# HBridge.net
KiCad netlist of a schematic drawn in Altium Designer
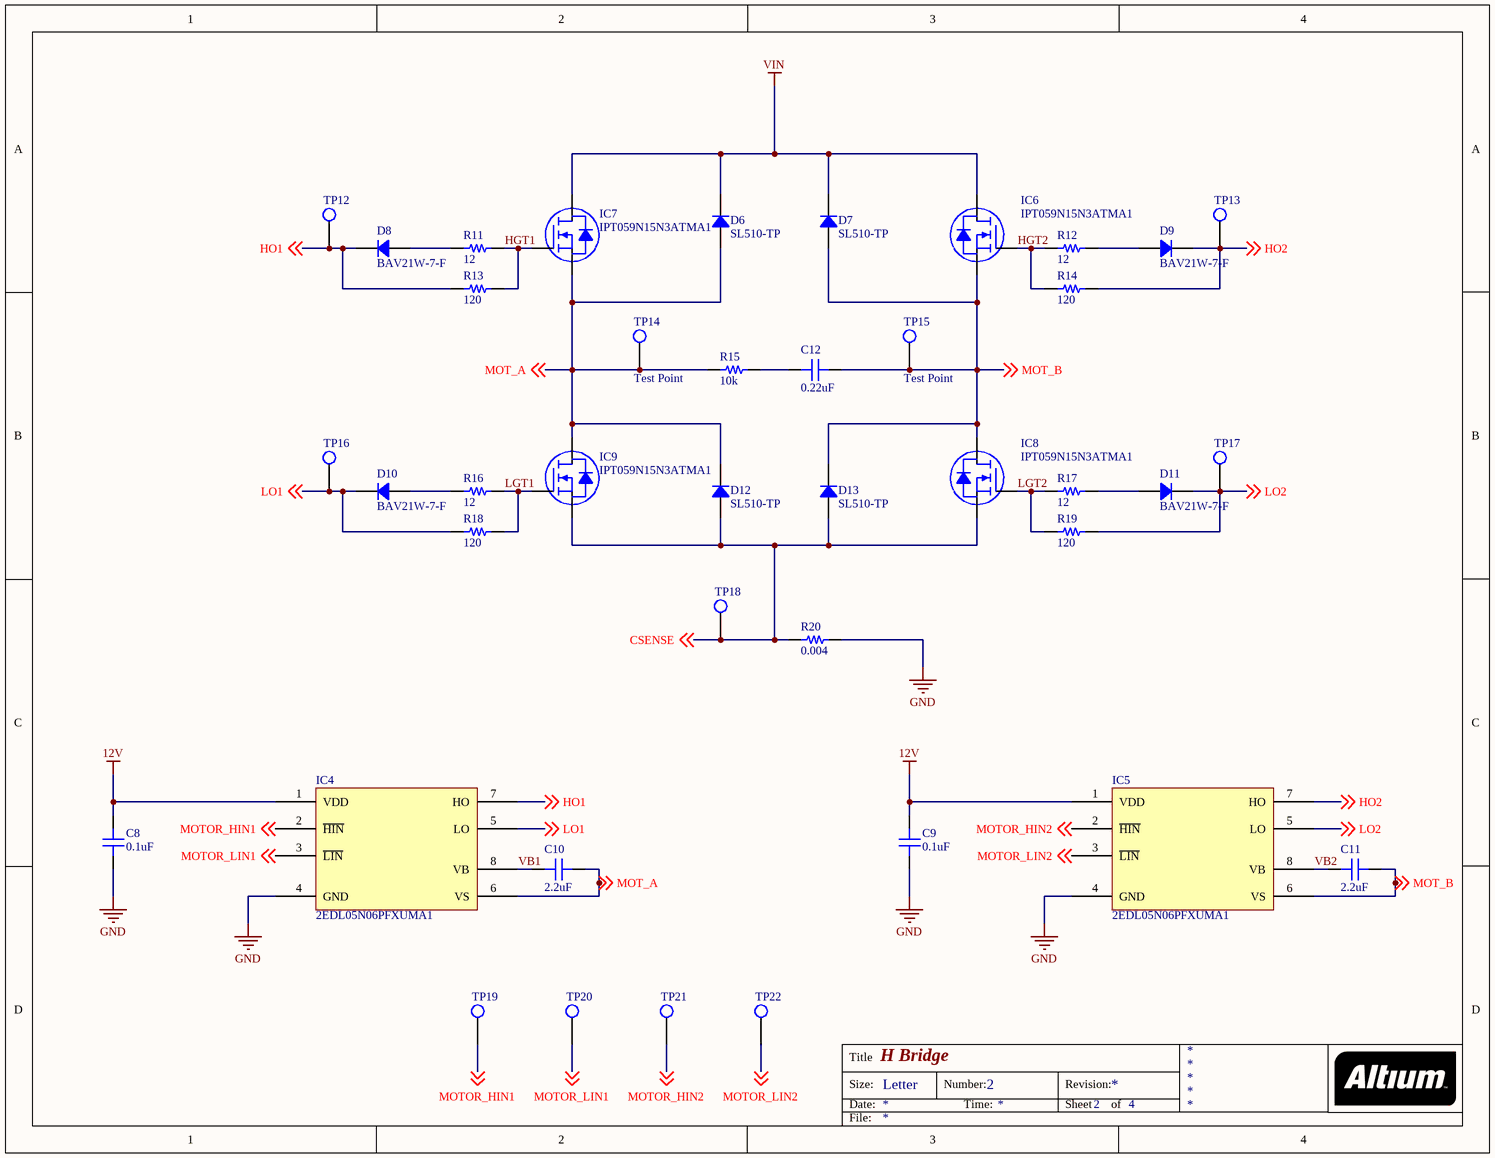
[diagram p0: HBridge.SchDoc]

(export (version "E")
  (design (tool "Eeschema 10.0.6"))
  (components
    (comp (ref "C8")
      (value "0.1uF")
      (footprint "CAP 0603/1608")
      (description "CAP CER 0.1UF 16V X7R 0603")
      (fields (field (name "PART NUMBER") "CC0603KPX7R7BB104") (field (name "MANUFACTURER") "Yageo"))
      (libsource (lib "Celestial Library Database") (part "Capacitor"))
    )
    (comp (ref "C9")
      (value "0.1uF")
      (footprint "CAP 0603/1608")
      (description "CAP CER 0.1UF 16V X7R 0603")
      (fields (field (name "PART NUMBER") "CC0603KPX7R7BB104") (field (name "MANUFACTURER") "Yageo"))
      (libsource (lib "Celestial Library Database") (part "Capacitor"))
    )
    (comp (ref "C10")
      (value "2.2uF")
      (footprint "CAP 0805/2012")
      (description "CAP CER 2.2UF 25V X6S 0805")
      (fields
        (field (name "PART NUMBER") "GRM219C81E225KE15D")
        (field (name "MANUFACTURER") "Murata Electronics North America")
      )
      (libsource (lib "Celestial Library Database") (part "Capacitor"))
    )
    (comp (ref "C11")
      (value "2.2uF")
      (footprint "CAP 0805/2012")
      (description "CAP CER 2.2UF 25V X6S 0805")
      (fields
        (field (name "PART NUMBER") "GRM219C81E225KE15D")
        (field (name "MANUFACTURER") "Murata Electronics North America")
      )
      (libsource (lib "Celestial Library Database") (part "Capacitor"))
    )
    (comp (ref "C12")
      (value "0.22uF")
      (footprint "CAP 1206/3216")
      (description "CAP CER 0.22UF 250V X7T 1206")
      (fields
        (field (name "PART NUMBER") "C3216X7T2E224K160AA")
        (field (name "MANUFACTURER") "TDK Corporation")
      )
      (libsource (lib "Celestial Library Database") (part "Capacitor"))
    )
    (comp (ref "D6")
      (value "SL510-TP")
      (footprint "ST DO214AB SMC")
      (description "DIODE SCHOTTKY 100V 5A DO214AB")
      (fields (field (name "MANUFACTURER") "Micro Commercial Co"))
      (libsource (lib "Celestial Library Database") (part "Diode"))
    )
    (comp (ref "D7")
      (value "SL510-TP")
      (footprint "ST DO214AB SMC")
      (description "DIODE SCHOTTKY 100V 5A DO214AB")
      (fields (field (name "MANUFACTURER") "Micro Commercial Co"))
      (libsource (lib "Celestial Library Database") (part "Diode"))
    )
    (comp (ref "D8")
      (value "BAV21W-7-F")
      (footprint "SOD-123")
      (description "DIODE GEN PURP 200V 200MA SOD123")
      (fields (field (name "MANUFACTURER") "Diodes Incorporated"))
      (libsource (lib "Celestial Library Database") (part "Diode"))
    )
    (comp (ref "D9")
      (value "BAV21W-7-F")
      (footprint "SOD-123")
      (description "DIODE GEN PURP 200V 200MA SOD123")
      (fields (field (name "MANUFACTURER") "Diodes Incorporated"))
      (libsource (lib "Celestial Library Database") (part "Diode"))
    )
    (comp (ref "D10")
      (value "BAV21W-7-F")
      (footprint "SOD-123")
      (description "DIODE GEN PURP 200V 200MA SOD123")
      (fields (field (name "MANUFACTURER") "Diodes Incorporated"))
      (libsource (lib "Celestial Library Database") (part "Diode"))
    )
    (comp (ref "D11")
      (value "BAV21W-7-F")
      (footprint "SOD-123")
      (description "DIODE GEN PURP 200V 200MA SOD123")
      (fields (field (name "MANUFACTURER") "Diodes Incorporated"))
      (libsource (lib "Celestial Library Database") (part "Diode"))
    )
    (comp (ref "D12")
      (value "SL510-TP")
      (footprint "ST DO214AB SMC")
      (description "DIODE SCHOTTKY 100V 5A DO214AB")
      (fields (field (name "MANUFACTURER") "Micro Commercial Co"))
      (libsource (lib "Celestial Library Database") (part "Diode"))
    )
    (comp (ref "D13")
      (value "SL510-TP")
      (footprint "ST DO214AB SMC")
      (description "DIODE SCHOTTKY 100V 5A DO214AB")
      (fields (field (name "MANUFACTURER") "Micro Commercial Co"))
      (libsource (lib "Celestial Library Database") (part "Diode"))
    )
    (comp (ref "IC4")
      (value "2EDL05N06PFXUMA1")
      (footprint "Infineon PG-DSO-8")
      (description "IC DRIVER GATE HALF BRIDGE 8DSO")
      (fields (field (name "MANUFACTURER") "Infineon Technologies"))
      (libsource (lib "Celestial Library Database") (part "Infineon 2EDL05N06PF"))
    )
    (comp (ref "IC5")
      (value "2EDL05N06PFXUMA1")
      (footprint "Infineon PG-DSO-8")
      (description "IC DRIVER GATE HALF BRIDGE 8DSO")
      (fields (field (name "MANUFACTURER") "Infineon Technologies"))
      (libsource (lib "Celestial Library Database") (part "Infineon 2EDL05N06PF"))
    )
    (comp (ref "IC6")
      (value "IPT059N15N3ATMA1")
      (footprint "INFINEON PG-HSOF-8-1")
      (description "MOSFET N-CH 150V 155A 8HSOF")
      (fields (field (name "MANUFACTURER") "Infineon Technologies"))
      (libsource (lib "Celestial Library Database") (part "INFINEON MOSFET IPT059N15N3"))
    )
    (comp (ref "IC7")
      (value "IPT059N15N3ATMA1")
      (footprint "INFINEON PG-HSOF-8-1")
      (description "MOSFET N-CH 150V 155A 8HSOF")
      (fields (field (name "MANUFACTURER") "Infineon Technologies"))
      (libsource (lib "") (part "INFINEON MOSFET IPT059N15N3_1"))
    )
    (comp (ref "IC8")
      (value "IPT059N15N3ATMA1")
      (footprint "INFINEON PG-HSOF-8-1")
      (description "MOSFET N-CH 150V 155A 8HSOF")
      (fields (field (name "MANUFACTURER") "Infineon Technologies"))
      (libsource (lib "Celestial Library Database") (part "INFINEON MOSFET IPT059N15N3"))
    )
    (comp (ref "IC9")
      (value "IPT059N15N3ATMA1")
      (footprint "INFINEON PG-HSOF-8-1")
      (description "MOSFET N-CH 150V 155A 8HSOF")
      (fields (field (name "MANUFACTURER") "Infineon Technologies"))
      (libsource (lib "") (part "INFINEON MOSFET IPT059N15N3_1"))
    )
    (comp (ref "R11")
      (value "12")
      (footprint "RES 1206/3216")
      (description "RES SMD 12 OHM 5% 1/4W 1206")
      (fields
        (field (name "PART NUMBER") "ERJ-8GEYJ120V")
        (field (name "MANUFACTURER") "Panasonic Electronic Components")
      )
      (libsource (lib "Celestial Library Database") (part "Resistor"))
    )
    (comp (ref "R12")
      (value "12")
      (footprint "RES 1206/3216")
      (description "RES SMD 12 OHM 5% 1/4W 1206")
      (fields
        (field (name "PART NUMBER") "ERJ-8GEYJ120V")
        (field (name "MANUFACTURER") "Panasonic Electronic Components")
      )
      (libsource (lib "Celestial Library Database") (part "Resistor"))
    )
    (comp (ref "R13")
      (value "120")
      (footprint "RES 1206/3216")
      (description "RES SMD 120 OHM 5% 1/4W 1206")
      (fields
        (field (name "PART NUMBER") "ERJ-8GEYJ121V")
        (field (name "MANUFACTURER") "Panasonic Electronic Components")
      )
      (libsource (lib "Celestial Library Database") (part "Resistor"))
    )
    (comp (ref "R14")
      (value "120")
      (footprint "RES 1206/3216")
      (description "RES SMD 120 OHM 5% 1/4W 1206")
      (fields
        (field (name "PART NUMBER") "ERJ-8GEYJ121V")
        (field (name "MANUFACTURER") "Panasonic Electronic Components")
      )
      (libsource (lib "Celestial Library Database") (part "Resistor"))
    )
    (comp (ref "R15")
      (value "10k")
      (footprint "RES 0805/2012")
      (description "RES SMD 10K OHM 5% 1/8W 0805")
      (fields
        (field (name "PART NUMBER") "ERJ-6GEYJ103V")
        (field (name "MANUFACTURER") "Panasonic Electronic Components")
      )
      (libsource (lib "Celestial Library Database") (part "Resistor"))
    )
    (comp (ref "R16")
      (value "12")
      (footprint "RES 1206/3216")
      (description "RES SMD 12 OHM 5% 1/4W 1206")
      (fields
        (field (name "PART NUMBER") "ERJ-8GEYJ120V")
        (field (name "MANUFACTURER") "Panasonic Electronic Components")
      )
      (libsource (lib "Celestial Library Database") (part "Resistor"))
    )
    (comp (ref "R17")
      (value "12")
      (footprint "RES 1206/3216")
      (description "RES SMD 12 OHM 5% 1/4W 1206")
      (fields
        (field (name "PART NUMBER") "ERJ-8GEYJ120V")
        (field (name "MANUFACTURER") "Panasonic Electronic Components")
      )
      (libsource (lib "Celestial Library Database") (part "Resistor"))
    )
    (comp (ref "R18")
      (value "120")
      (footprint "RES 1206/3216")
      (description "RES SMD 120 OHM 5% 1/4W 1206")
      (fields
        (field (name "PART NUMBER") "ERJ-8GEYJ121V")
        (field (name "MANUFACTURER") "Panasonic Electronic Components")
      )
      (libsource (lib "Celestial Library Database") (part "Resistor"))
    )
    (comp (ref "R19")
      (value "120")
      (footprint "RES 1206/3216")
      (description "RES SMD 120 OHM 5% 1/4W 1206")
      (fields
        (field (name "PART NUMBER") "ERJ-8GEYJ121V")
        (field (name "MANUFACTURER") "Panasonic Electronic Components")
      )
      (libsource (lib "Celestial Library Database") (part "Resistor"))
    )
    (comp (ref "R20")
      (value "0.004")
      (footprint "STACKPOLE CSR2512")
      (description "RES SMD 0.004 OHM 1% 1W 2512")
      (fields
        (field (name "PART NUMBER") "ERJ-MP4MF4M0U")
        (field (name "MANUFACTURER") "Panasonic Electronic Components")
      )
      (libsource (lib "Celestial Library Database") (part "Resistor"))
    )
    (comp (ref "TP12")
      (value "Test Point")
      (footprint "Test Point")
      (libsource (lib "Motor Controller") (part "Test Point"))
    )
    (comp (ref "TP13")
      (value "Test Point")
      (footprint "Test Point")
      (libsource (lib "Motor Controller") (part "Test Point"))
    )
    (comp (ref "TP14")
      (value "Test Point")
      (footprint "Test Point")
      (libsource (lib "Motor Controller") (part "Test Point"))
    )
    (comp (ref "TP15")
      (value "Test Point")
      (footprint "Test Point")
      (libsource (lib "Motor Controller") (part "Test Point"))
    )
    (comp (ref "TP16")
      (value "Test Point")
      (footprint "Test Point")
      (libsource (lib "Motor Controller") (part "Test Point"))
    )
    (comp (ref "TP17")
      (value "Test Point")
      (footprint "Test Point")
      (libsource (lib "Motor Controller") (part "Test Point"))
    )
    (comp (ref "TP18")
      (value "Test Point")
      (footprint "Test Point")
      (libsource (lib "Motor Controller") (part "Test Point"))
    )
    (comp (ref "TP19")
      (value "Test Point")
      (footprint "Test Point")
      (libsource (lib "Motor Controller") (part "Test Point"))
    )
    (comp (ref "TP20")
      (value "Test Point")
      (footprint "Test Point")
      (libsource (lib "Motor Controller") (part "Test Point"))
    )
    (comp (ref "TP21")
      (value "Test Point")
      (footprint "Test Point")
      (libsource (lib "Motor Controller") (part "Test Point"))
    )
    (comp (ref "TP22")
      (value "Test Point")
      (footprint "Test Point")
      (libsource (lib "Motor Controller") (part "Test Point"))
    )
  )
  (nets
    (net (code "1") (name "/HGT1") (class "Default")
      (node (ref "IC7") (pin "G") (pinfunction "G_G") (pintype "passive"))
      (node (ref "R11") (pin "2") (pinfunction "2_2") (pintype "passive"))
      (node (ref "R13") (pin "2") (pinfunction "2_2") (pintype "passive"))
    )
    (net (code "2") (name "/HGT2") (class "Default")
      (node (ref "IC6") (pin "G") (pinfunction "G_G") (pintype "passive"))
      (node (ref "R12") (pin "1") (pinfunction "1_1") (pintype "passive"))
      (node (ref "R14") (pin "1") (pinfunction "1_1") (pintype "passive"))
    )
    (net (code "3") (name "/LGT1") (class "Default")
      (node (ref "IC9") (pin "G") (pinfunction "G_G") (pintype "passive"))
      (node (ref "R16") (pin "2") (pinfunction "2_2") (pintype "passive"))
      (node (ref "R18") (pin "2") (pinfunction "2_2") (pintype "passive"))
    )
    (net (code "4") (name "/LGT2") (class "Default")
      (node (ref "IC8") (pin "G") (pinfunction "G_G") (pintype "passive"))
      (node (ref "R17") (pin "1") (pinfunction "1_1") (pintype "passive"))
      (node (ref "R19") (pin "1") (pinfunction "1_1") (pintype "passive"))
    )
    (net (code "5") (name "/VB1") (class "Default")
      (node (ref "C10") (pin "2") (pinfunction "2_2") (pintype "passive"))
      (node (ref "IC4") (pin "8") (pinfunction "VB_8") (pintype "passive"))
    )
    (net (code "6") (name "/VB2") (class "Default")
      (node (ref "C11") (pin "2") (pinfunction "2_2") (pintype "passive"))
      (node (ref "IC5") (pin "8") (pinfunction "VB_8") (pintype "passive"))
    )
    (net (code "7") (name "12V") (class "Default")
      (node (ref "C8") (pin "2") (pinfunction "2_2") (pintype "passive"))
      (node (ref "C9") (pin "2") (pinfunction "2_2") (pintype "passive"))
      (node (ref "IC4") (pin "1") (pinfunction "VDD_1") (pintype "passive"))
      (node (ref "IC5") (pin "1") (pinfunction "VDD_1") (pintype "passive"))
    )
    (net (code "8") (name "CSENSE") (class "Default")
      (node (ref "D12") (pin "1") (pinfunction "1_1") (pintype "passive"))
      (node (ref "D13") (pin "1") (pinfunction "1_1") (pintype "passive"))
      (node (ref "IC8") (pin "S") (pinfunction "S_S") (pintype "passive"))
      (node (ref "IC9") (pin "S") (pinfunction "S_S") (pintype "passive"))
      (node (ref "R20") (pin "1") (pinfunction "1_1") (pintype "passive"))
      (node (ref "TP18") (pin "1") (pinfunction "TP_1") (pintype "passive"))
    )
    (net (code "9") (name "GND") (class "Default")
      (node (ref "C8") (pin "1") (pinfunction "1_1") (pintype "passive"))
      (node (ref "C9") (pin "1") (pinfunction "1_1") (pintype "passive"))
      (node (ref "IC4") (pin "4") (pinfunction "GND_4") (pintype "passive"))
      (node (ref "IC5") (pin "4") (pinfunction "GND_4") (pintype "passive"))
      (node (ref "R20") (pin "2") (pinfunction "2_2") (pintype "passive"))
    )
    (net (code "10") (name "HO1") (class "Default")
      (node (ref "D8") (pin "2") (pinfunction "2_2") (pintype "passive"))
      (node (ref "IC4") (pin "7") (pinfunction "HO_7") (pintype "passive"))
      (node (ref "R13") (pin "1") (pinfunction "1_1") (pintype "passive"))
      (node (ref "TP12") (pin "1") (pinfunction "TP_1") (pintype "passive"))
    )
    (net (code "11") (name "HO2") (class "Default")
      (node (ref "D9") (pin "2") (pinfunction "2_2") (pintype "passive"))
      (node (ref "IC5") (pin "7") (pinfunction "HO_7") (pintype "passive"))
      (node (ref "R14") (pin "2") (pinfunction "2_2") (pintype "passive"))
      (node (ref "TP13") (pin "1") (pinfunction "TP_1") (pintype "passive"))
    )
    (net (code "12") (name "LO1") (class "Default")
      (node (ref "D10") (pin "2") (pinfunction "2_2") (pintype "passive"))
      (node (ref "IC4") (pin "5") (pinfunction "LO_5") (pintype "passive"))
      (node (ref "R18") (pin "1") (pinfunction "1_1") (pintype "passive"))
      (node (ref "TP16") (pin "1") (pinfunction "TP_1") (pintype "passive"))
    )
    (net (code "13") (name "LO2") (class "Default")
      (node (ref "D11") (pin "2") (pinfunction "2_2") (pintype "passive"))
      (node (ref "IC5") (pin "5") (pinfunction "LO_5") (pintype "passive"))
      (node (ref "R19") (pin "2") (pinfunction "2_2") (pintype "passive"))
      (node (ref "TP17") (pin "1") (pinfunction "TP_1") (pintype "passive"))
    )
    (net (code "14") (name "MOTOR_HIN1") (class "Default")
      (node (ref "IC4") (pin "2") (pinfunction "~{HIN}_2") (pintype "passive"))
      (node (ref "TP19") (pin "1") (pinfunction "TP_1") (pintype "passive"))
    )
    (net (code "15") (name "MOTOR_HIN2") (class "Default")
      (node (ref "IC5") (pin "2") (pinfunction "~{HIN}_2") (pintype "passive"))
      (node (ref "TP21") (pin "1") (pinfunction "TP_1") (pintype "passive"))
    )
    (net (code "16") (name "MOTOR_LIN1") (class "Default")
      (node (ref "IC4") (pin "3") (pinfunction "~{LIN}_3") (pintype "passive"))
      (node (ref "TP20") (pin "1") (pinfunction "TP_1") (pintype "passive"))
    )
    (net (code "17") (name "MOTOR_LIN2") (class "Default")
      (node (ref "IC5") (pin "3") (pinfunction "~{LIN}_3") (pintype "passive"))
      (node (ref "TP22") (pin "1") (pinfunction "TP_1") (pintype "passive"))
    )
    (net (code "18") (name "MOT_A") (class "Default")
      (node (ref "C10") (pin "1") (pinfunction "1_1") (pintype "passive"))
      (node (ref "D12") (pin "2") (pinfunction "2_2") (pintype "passive"))
      (node (ref "D6") (pin "1") (pinfunction "1_1") (pintype "passive"))
      (node (ref "IC4") (pin "6") (pinfunction "VS_6") (pintype "passive"))
      (node (ref "IC7") (pin "S") (pinfunction "S_S") (pintype "passive"))
      (node (ref "IC9") (pin "D") (pinfunction "D_D") (pintype "passive"))
      (node (ref "R15") (pin "1") (pinfunction "1_1") (pintype "passive"))
      (node (ref "TP14") (pin "1") (pinfunction "TP_1") (pintype "passive"))
    )
    (net (code "19") (name "MOT_B") (class "Default")
      (node (ref "C11") (pin "1") (pinfunction "1_1") (pintype "passive"))
      (node (ref "C12") (pin "2") (pinfunction "2_2") (pintype "passive"))
      (node (ref "D13") (pin "2") (pinfunction "2_2") (pintype "passive"))
      (node (ref "D7") (pin "1") (pinfunction "1_1") (pintype "passive"))
      (node (ref "IC5") (pin "6") (pinfunction "VS_6") (pintype "passive"))
      (node (ref "IC6") (pin "S") (pinfunction "S_S") (pintype "passive"))
      (node (ref "IC8") (pin "D") (pinfunction "D_D") (pintype "passive"))
      (node (ref "TP15") (pin "1") (pinfunction "TP_1") (pintype "passive"))
    )
    (net (code "20") (name "Net-(C12-Pad1)") (class "Default")
      (node (ref "C12") (pin "1") (pinfunction "1_1") (pintype "passive"))
      (node (ref "R15") (pin "2") (pinfunction "2_2") (pintype "passive"))
    )
    (net (code "21") (name "Net-(D8-Pad1)") (class "Default")
      (node (ref "D8") (pin "1") (pinfunction "1_1") (pintype "passive"))
      (node (ref "R11") (pin "1") (pinfunction "1_1") (pintype "passive"))
    )
    (net (code "22") (name "Net-(D9-Pad1)") (class "Default")
      (node (ref "D9") (pin "1") (pinfunction "1_1") (pintype "passive"))
      (node (ref "R12") (pin "2") (pinfunction "2_2") (pintype "passive"))
    )
    (net (code "23") (name "Net-(D10-Pad1)") (class "Default")
      (node (ref "D10") (pin "1") (pinfunction "1_1") (pintype "passive"))
      (node (ref "R16") (pin "1") (pinfunction "1_1") (pintype "passive"))
    )
    (net (code "24") (name "Net-(D11-Pad1)") (class "Default")
      (node (ref "D11") (pin "1") (pinfunction "1_1") (pintype "passive"))
      (node (ref "R17") (pin "2") (pinfunction "2_2") (pintype "passive"))
    )
    (net (code "25") (name "VIN") (class "Default")
      (node (ref "D6") (pin "2") (pinfunction "2_2") (pintype "passive"))
      (node (ref "D7") (pin "2") (pinfunction "2_2") (pintype "passive"))
      (node (ref "IC6") (pin "D") (pinfunction "D_D") (pintype "passive"))
      (node (ref "IC7") (pin "D") (pinfunction "D_D") (pintype "passive"))
    )
  )
)
